# Fuel_gauge.net
KiCad netlist of a schematic drawn in Altium Designer
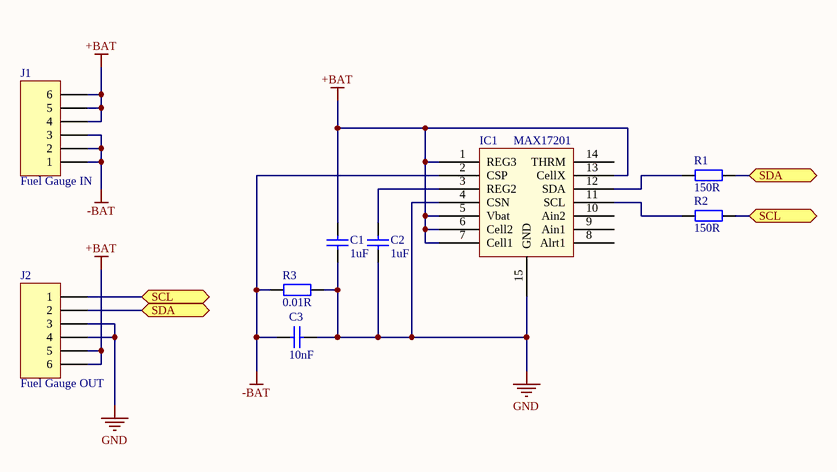
[diagram p0: Fuel gauge.SchDoc]

(export (version "E")
  (design (tool "Eeschema 10.0.6"))
  (components
    (comp (ref "C1")
      (value "1uF")
      (footprint "0603 cap")
      (description "Capacitor")
      (fields (field (name "VOLTAGE") ">5V"))
      (libsource (lib "IKSOR_LIB_main") (part "Capacitor NP"))
    )
    (comp (ref "C2")
      (value "1uF")
      (footprint "0603 cap")
      (description "Capacitor")
      (fields (field (name "VOLTAGE") ">5V"))
      (libsource (lib "IKSOR_LIB_main") (part "Capacitor NP"))
    )
    (comp (ref "C3")
      (value "10nF")
      (footprint "0603 cap")
      (description "Capacitor")
      (fields (field (name "VOLTAGE") ">5V"))
      (libsource (lib "IKSOR_LIB_main") (part "Capacitor NP"))
    )
    (comp (ref "IC1")
      (value "MAX17201")
      (footprint "TDFN14")
      (description "Single cell fuel gauge")
      (libsource (lib "IKSOR_LIB_main") (part "MAX17201"))
    )
    (comp (ref "J1")
      (value "Fuel Gauge IN")
      (footprint "HDR1X6")
      (description "Header, 6-Pin")
      (fields (field (name "PUBLISHER") "Altium Limited"))
      (libsource (lib "Miscellaneous Connectors") (part "Header 6"))
    )
    (comp (ref "J2")
      (value "Fuel Gauge OUT")
      (footprint "HDR1X6")
      (description "Header, 6-Pin")
      (fields (field (name "PUBLISHER") "Altium Limited"))
      (libsource (lib "") (part "Header 6_1"))
    )
    (comp (ref "R1")
      (value "150R")
      (footprint "0603 RES")
      (description "Resistor SMD")
      (fields (field (name "Comment") "Resistor generic"))
      (libsource (lib "IKSOR_LIB_main") (part "Resistor"))
    )
    (comp (ref "R2")
      (value "150R")
      (footprint "0603 RES")
      (description "Resistor SMD")
      (fields (field (name "Comment") "Resistor generic"))
      (libsource (lib "IKSOR_LIB_main") (part "Resistor"))
    )
    (comp (ref "R3")
      (value "0.01R")
      (footprint "2512 RES")
      (description "Resistor SMD")
      (fields (field (name "Comment") "Resistor generic"))
      (libsource (lib "IKSOR_LIB_main") (part "Resistor"))
    )
  )
  (nets
    (net (code "1") (name "+BAT") (class "Default")
      (node (ref "C1") (pin "2") (pinfunction "2_2") (pintype "passive"))
      (node (ref "IC1") (pin "1") (pinfunction "REG3_1") (pintype "passive"))
      (node (ref "IC1") (pin "13") (pinfunction "CellX_13") (pintype "passive"))
      (node (ref "IC1") (pin "5") (pinfunction "Vbat_5") (pintype "passive"))
      (node (ref "IC1") (pin "6") (pinfunction "Cell2_6") (pintype "passive"))
      (node (ref "IC1") (pin "7") (pinfunction "Cell1_7") (pintype "passive"))
      (node (ref "J1") (pin "4") (pinfunction "4_4") (pintype "passive"))
      (node (ref "J1") (pin "5") (pinfunction "5_5") (pintype "passive"))
      (node (ref "J1") (pin "6") (pinfunction "6_6") (pintype "passive"))
      (node (ref "J2") (pin "5") (pinfunction "5_5") (pintype "passive"))
      (node (ref "J2") (pin "6") (pinfunction "6_6") (pintype "passive"))
    )
    (net (code "2") (name "-BAT") (class "Default")
      (node (ref "C3") (pin "2") (pinfunction "2_2") (pintype "passive"))
      (node (ref "IC1") (pin "2") (pinfunction "CSP_2") (pintype "passive"))
      (node (ref "J1") (pin "1") (pinfunction "1_1") (pintype "passive"))
      (node (ref "J1") (pin "2") (pinfunction "2_2") (pintype "passive"))
      (node (ref "J1") (pin "3") (pinfunction "3_3") (pintype "passive"))
      (node (ref "R3") (pin "1") (pinfunction "1_1") (pintype "passive"))
    )
    (net (code "3") (name "/SCL") (class "Default")
      (node (ref "J2") (pin "1") (pinfunction "1_1") (pintype "passive"))
      (node (ref "R2") (pin "2") (pinfunction "2_2") (pintype "passive"))
    )
    (net (code "4") (name "/SDA") (class "Default")
      (node (ref "J2") (pin "2") (pinfunction "2_2") (pintype "passive"))
      (node (ref "R1") (pin "2") (pinfunction "2_2") (pintype "passive"))
    )
    (net (code "5") (name "GND") (class "Default")
      (node (ref "C1") (pin "1") (pinfunction "1_1") (pintype "passive"))
      (node (ref "C2") (pin "1") (pinfunction "1_1") (pintype "passive"))
      (node (ref "C3") (pin "1") (pinfunction "1_1") (pintype "passive"))
      (node (ref "IC1") (pin "15") (pinfunction "GND_15") (pintype "passive"))
      (node (ref "IC1") (pin "4") (pinfunction "CSN_4") (pintype "passive"))
      (node (ref "J2") (pin "3") (pinfunction "3_3") (pintype "passive"))
      (node (ref "J2") (pin "4") (pinfunction "4_4") (pintype "passive"))
      (node (ref "R3") (pin "2") (pinfunction "2_2") (pintype "passive"))
    )
    (net (code "6") (name "Net-(IC1-REG2)") (class "Default")
      (node (ref "C2") (pin "2") (pinfunction "2_2") (pintype "passive"))
      (node (ref "IC1") (pin "3") (pinfunction "REG2_3") (pintype "passive"))
    )
    (net (code "7") (name "Net-(IC1-SCL)") (class "Default")
      (node (ref "IC1") (pin "11") (pinfunction "SCL_11") (pintype "passive"))
      (node (ref "R2") (pin "1") (pinfunction "1_1") (pintype "passive"))
    )
    (net (code "8") (name "Net-(IC1-SDA)") (class "Default")
      (node (ref "IC1") (pin "12") (pinfunction "SDA_12") (pintype "passive"))
      (node (ref "R1") (pin "1") (pinfunction "1_1") (pintype "passive"))
    )
    (net (code "9") (name "unconnected-(IC1-Ain1-Pad9)") (class "Default")
      (node (ref "IC1") (pin "9") (pinfunction "Ain1_9") (pintype "passive"))
    )
    (net (code "10") (name "unconnected-(IC1-Ain2-Pad10)") (class "Default")
      (node (ref "IC1") (pin "10") (pinfunction "Ain2_10") (pintype "passive"))
    )
    (net (code "11") (name "unconnected-(IC1-Alrt1-Pad8)") (class "Default")
      (node (ref "IC1") (pin "8") (pinfunction "Alrt1_8") (pintype "passive"))
    )
    (net (code "12") (name "unconnected-(IC1-THRM-Pad14)") (class "Default")
      (node (ref "IC1") (pin "14") (pinfunction "THRM_14") (pintype "passive"))
    )
  )
)
